# main.net
KiCad netlist of a schematic drawn in Altium Designer
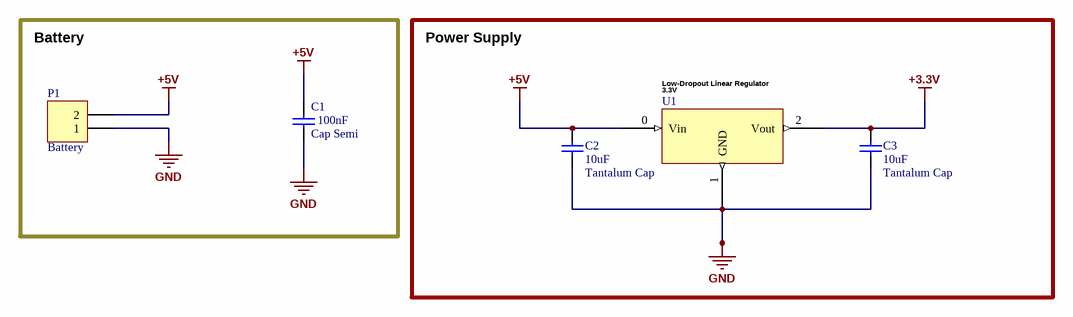
[diagram p0: main.SchDoc]

(export (version "E")
  (design (tool "Eeschema 10.0.6"))
  (components
    (comp (ref "C1")
      (value "Cap Semi")
      (footprint "C1206")
      (description "Capacitor (Semiconductor SIM Model)")
      (fields (field (name "ALTIUM_VALUE") "100nF") (field (name "PUBLISHER") "Altium Limited"))
      (libsource (lib "Miscellaneous Devices") (part "Cap Semi"))
    )
    (comp (ref "C2")
      (value "Tantalum Cap")
      (footprint "C1206")
      (description "Capacitor (Semiconductor SIM Model)")
      (fields (field (name "ALTIUM_VALUE") "10uF") (field (name "PUBLISHER") "Altium Limited"))
      (libsource (lib "Miscellaneous Devices") (part "Cap Semi"))
    )
    (comp (ref "C3")
      (value "Tantalum Cap")
      (footprint "C1206")
      (description "Capacitor (Semiconductor SIM Model)")
      (fields (field (name "ALTIUM_VALUE") "10uF") (field (name "PUBLISHER") "Altium Limited"))
      (libsource (lib "Miscellaneous Devices") (part "Cap Semi"))
    )
    (comp (ref "P1")
      (value "Battery")
      (footprint "HDR1X2H")
      (description "Header, 2-Pin, Right Angle")
      (fields (field (name "VOLTAGE") "9V") (field (name "PUBLISHER") "Altium Limited"))
      (libsource (lib "Miscellaneous Connectors") (part "Header 2H"))
    )
    (comp (ref "U1")
      (value "Low-Dropout Linear Regulator")
      (footprint "4-Pin SOT")
      (fields (field (name "OUTPUT VOLTAGE") "3.3V"))
      (libsource (lib "mylib") (part "lm1117"))
    )
  )
  (nets
    (net (code "1") (name "+3.3V") (class "Default")
      (node (ref "C3") (pin "2") (pinfunction "2_2") (pintype "passive"))
      (node (ref "U1") (pin "2") (pinfunction "Vout_2") (pintype "output"))
    )
    (net (code "2") (name "+5V") (class "Default")
      (node (ref "C1") (pin "2") (pinfunction "2_2") (pintype "passive"))
      (node (ref "C2") (pin "2") (pinfunction "2_2") (pintype "passive"))
      (node (ref "P1") (pin "2") (pinfunction "2_2") (pintype "passive"))
      (node (ref "U1") (pin "0") (pinfunction "Vin_0") (pintype "input"))
    )
    (net (code "3") (name "GND") (class "Default")
      (node (ref "C1") (pin "1") (pinfunction "1_1") (pintype "passive"))
      (node (ref "C2") (pin "1") (pinfunction "1_1") (pintype "passive"))
      (node (ref "C3") (pin "1") (pinfunction "1_1") (pintype "passive"))
      (node (ref "P1") (pin "1") (pinfunction "1_1") (pintype "passive"))
      (node (ref "U1") (pin "1") (pinfunction "GND_1") (pintype "output"))
    )
  )
)
